# Boot.net
KiCad netlist of a schematic drawn in Altium Designer
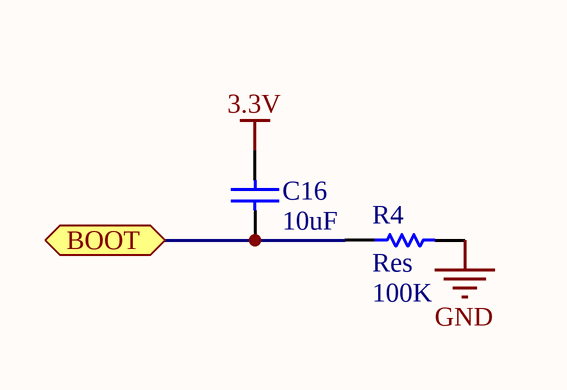
[diagram p0: Boot.SchDoc]

(export (version "E")
  (design (tool "Eeschema 10.0.6"))
  (components
    (comp (ref "C16")
      (value "10uF")
      (footprint "2012[0805]")
      (description "Capacitor")
      (fields (field (name "Comment") "Cap_UP") (field (name "PUBLISHER") "Altium Limited"))
      (libsource (lib "KN2CLib") (part "Cap_UP"))
    )
    (comp (ref "R4")
      (value "Res")
      (footprint "2012[0805]")
      (description "Semiconductor Resistor")
      (fields (field (name "ALTIUM_VALUE") "100K") (field (name "PUBLISHER") "Altium Limited"))
      (libsource (lib "KN2CLib") (part "Res"))
    )
  )
  (nets
    (net (code "1") (name "/BOOT") (class "Default")
      (node (ref "C16") (pin "2") (pinfunction "2_2") (pintype "passive"))
      (node (ref "R4") (pin "1") (pinfunction "1_1") (pintype "passive"))
    )
    (net (code "2") (name "3.3V") (class "Default")
      (node (ref "C16") (pin "1") (pinfunction "1_1") (pintype "passive"))
    )
    (net (code "3") (name "GND") (class "Default")
      (node (ref "R4") (pin "2") (pinfunction "2_2") (pintype "passive"))
    )
  )
)
